# HT32F52352.net
KiCad netlist of a schematic drawn in Altium Designer
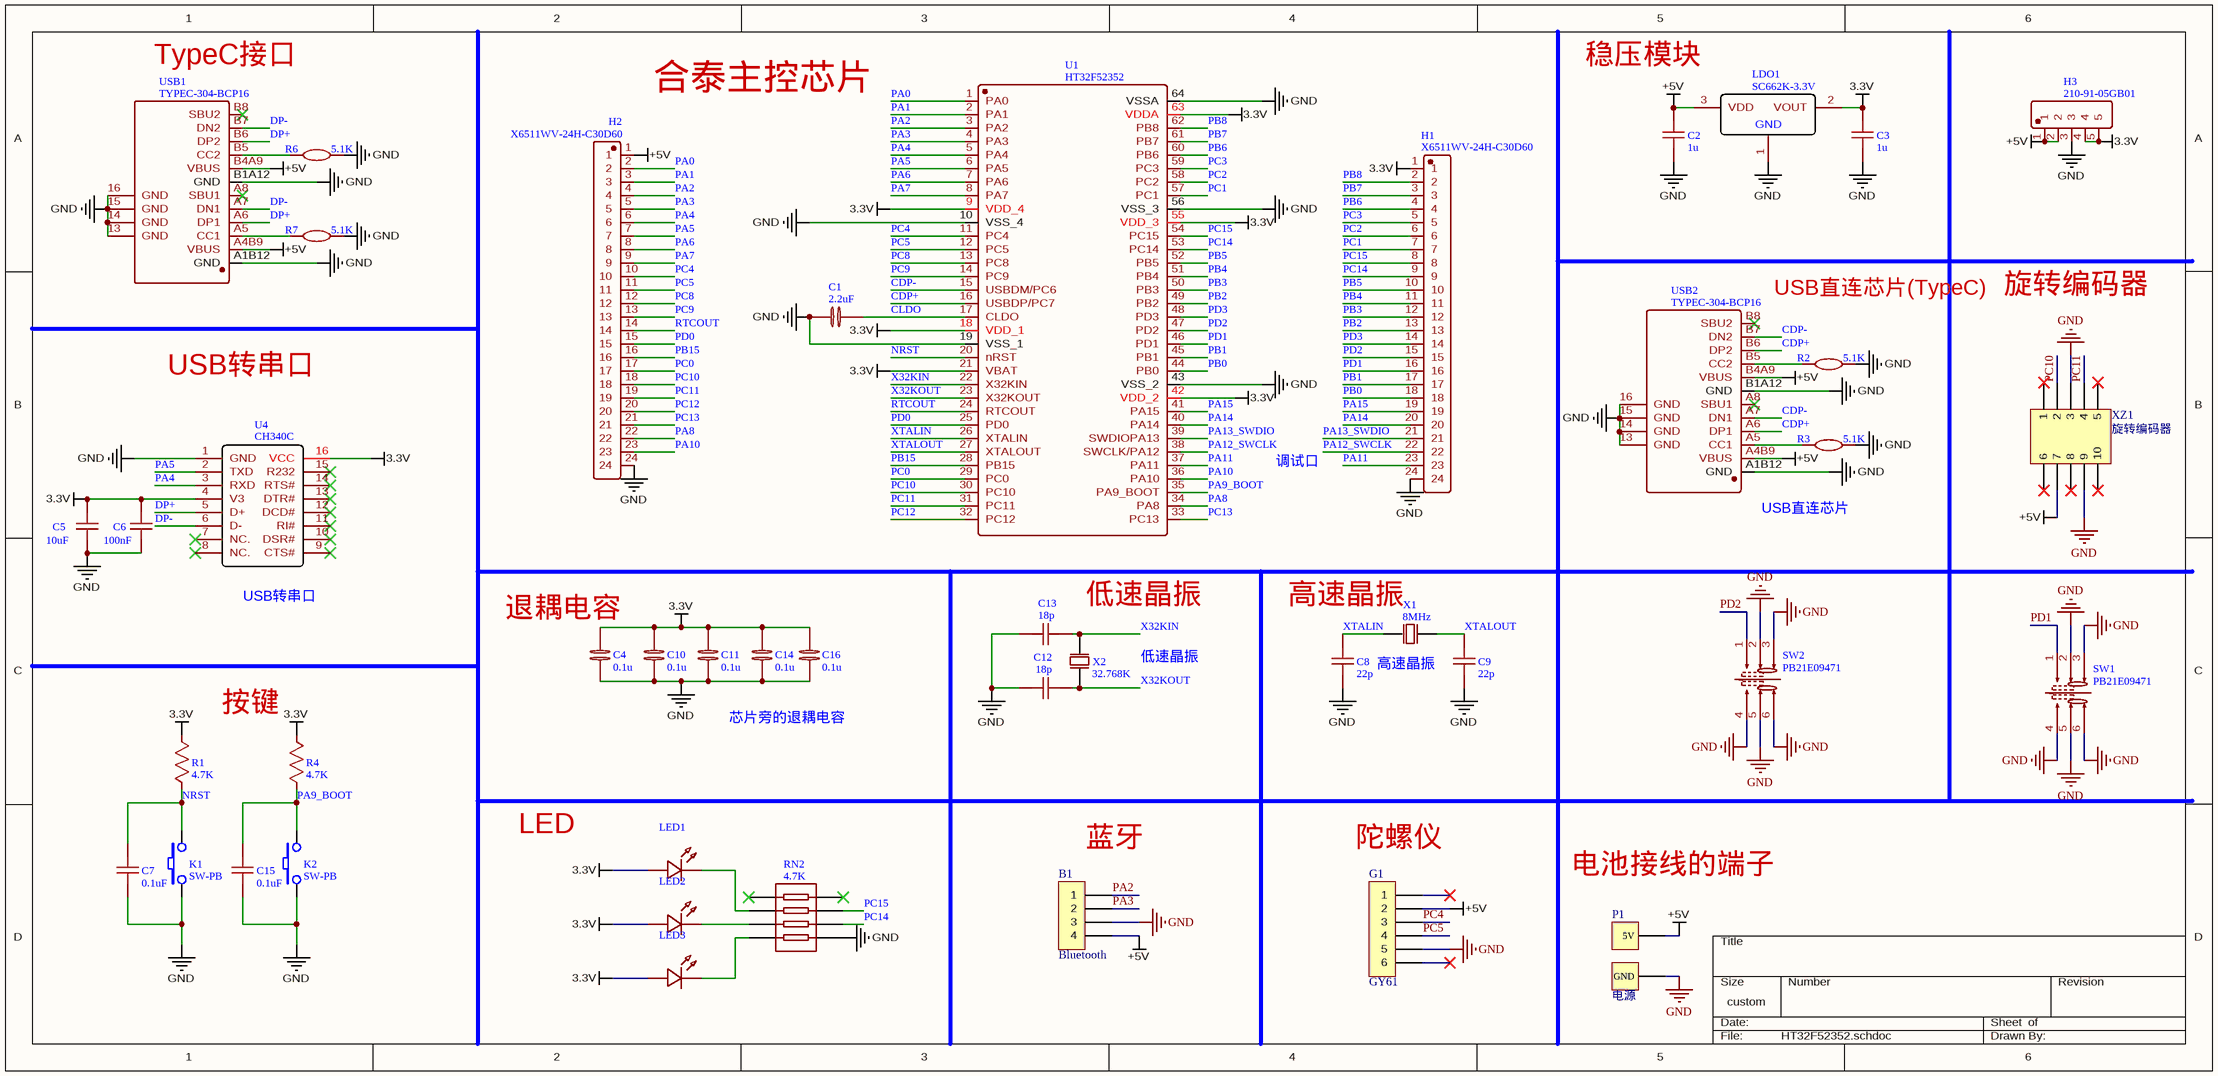
[diagram p0: HT32F52352.schdoc]

(export (version "E")
  (design (tool "Eeschema 10.0.6"))
  (components
    (comp (ref "B1") (value "Bluetooth") (footprint "HDR1X4") (libsource (lib "HT32") (part "Bluetooth")))
    (comp (ref "C1")
      (value "2.2uF")
      (footprint "0805_C")
      (fields (field (name "CONTRIBUTOR") "LCEDA_Lib"))
      (libsource (lib "altium-import") (part "root_0_2.2uF_"))
    )
    (comp (ref "C2")
      (value "1u")
      (footprint "0805_C")
      (fields (field (name "CONTRIBUTOR") "LCEDA_Lib"))
      (libsource (lib "altium-import") (part "root_1_1u_"))
    )
    (comp (ref "C3")
      (value "1u")
      (footprint "0805_C")
      (fields (field (name "CONTRIBUTOR") "LCEDA_Lib"))
      (libsource (lib "altium-import") (part "root_1_1u_"))
    )
    (comp (ref "C4")
      (value "0.1u")
      (footprint "0805_C")
      (fields (field (name "CONTRIBUTOR") "LCEDA_Lib"))
      (libsource (lib "altium-import") (part "root_1_0.1u_"))
    )
    (comp (ref "C5")
      (value "10uF")
      (footprint "0805_C")
      (libsource (lib "altium-import") (part "root_0_10uF_"))
    )
    (comp (ref "C6")
      (value "100nF")
      (footprint "0805_C")
      (libsource (lib "altium-import") (part "root_2_100nF_"))
    )
    (comp (ref "C7")
      (value "0.1uF")
      (footprint "0805_C")
      (libsource (lib "altium-import") (part "root_0_0.1uF_"))
    )
    (comp (ref "C8")
      (value "22p")
      (footprint "0805_C")
      (fields (field (name "CONTRIBUTOR") "LCEDA_Lib"))
      (libsource (lib "altium-import") (part "root_1_22p_"))
    )
    (comp (ref "C9")
      (value "22p")
      (footprint "0805_C")
      (fields (field (name "CONTRIBUTOR") "LCEDA_Lib"))
      (libsource (lib "altium-import") (part "root_1_22p_"))
    )
    (comp (ref "C10")
      (value "0.1u")
      (footprint "0805_C")
      (fields (field (name "CONTRIBUTOR") "LCEDA_Lib"))
      (libsource (lib "altium-import") (part "root_1_0.1u_"))
    )
    (comp (ref "C11")
      (value "0.1u")
      (footprint "0805_C")
      (fields (field (name "CONTRIBUTOR") "LCEDA_Lib"))
      (libsource (lib "altium-import") (part "root_1_0.1u_"))
    )
    (comp (ref "C12")
      (value "18p")
      (footprint "0805_C")
      (fields (field (name "CONTRIBUTOR") "LCEDA_Lib"))
      (libsource (lib "") (part "root_0_18p__1"))
    )
    (comp (ref "C13")
      (value "18p")
      (footprint "0805_C")
      (fields (field (name "CONTRIBUTOR") "LCEDA_Lib"))
      (libsource (lib "altium-import") (part "root_0_18p_"))
    )
    (comp (ref "C14")
      (value "0.1u")
      (footprint "0805_C")
      (fields (field (name "CONTRIBUTOR") "LCEDA_Lib"))
      (libsource (lib "altium-import") (part "root_1_0.1u_"))
    )
    (comp (ref "C15")
      (value "0.1uF")
      (footprint "0805_C")
      (libsource (lib "altium-import") (part "root_0_0.1uF_"))
    )
    (comp (ref "C16")
      (value "0.1u")
      (footprint "0805_C")
      (fields (field (name "CONTRIBUTOR") "LCEDA_Lib"))
      (libsource (lib "altium-import") (part "root_1_0.1u_"))
    )
    (comp (ref "G1") (value "GY61") (footprint "HDR1X6") (libsource (lib "HT32") (part "GY61")))
    (comp (ref "H1")
      (value "X6511WV-24H-C30D60")
      (footprint "HDR-TH_24P-P2.54-V-M")
      (fields (field (name "BOM_SUPPLIER PART") "C725956") (field (name "CONTRIBUTOR") "LCSC"))
      (libsource (lib "altium-import") (part "root_0_X6511WV-24H-C30D60_"))
    )
    (comp (ref "H2")
      (value "X6511WV-24H-C30D60")
      (footprint "HDR-TH_24P-P2.54-V-M")
      (fields (field (name "BOM_SUPPLIER PART") "C725956") (field (name "CONTRIBUTOR") "LCSC"))
      (libsource (lib "") (part "root_0_X6511WV-24H-C30D60__1"))
    )
    (comp (ref "H3")
      (value "210-91-05GB01")
      (footprint "HDR-TH_5P-P2.54-V-M")
      (fields (field (name "BOM_SUPPLIER PART") "C390682") (field (name "CONTRIBUTOR") "LCSC"))
      (libsource (lib "altium-import") (part "root_1_210-91-05GB01_"))
    )
    (comp (ref "K1")
      (value "SW-PB")
      (footprint "SW-SMD_L6.1-W3.7-LS7.9")
      (fields (field (name "CONTRIBUTOR") "ZhangYonghui"))
      (libsource (lib "altium-import") (part "root_3_SW-PB_"))
    )
    (comp (ref "K2")
      (value "SW-PB")
      (footprint "SW-SMD_L6.1-W3.7-LS7.9")
      (fields (field (name "CONTRIBUTOR") "ZhangYonghui"))
      (libsource (lib "altium-import") (part "root_3_SW-PB_"))
    )
    (comp (ref "LDO1")
      (value "SC662K-3.3V")
      (footprint "SOT-23-3_L2.9-W1.3-P1.90-LS2.4-BR")
      (fields (field (name "BOM_SUPPLIER PART") "C83932"))
      (libsource (lib "altium-import") (part "root_0_SC662K-3.3V_"))
    )
    (comp (ref "LED1")
      (value "LED-0603_B")
      (footprint "LED0603_BLUE")
      (fields
        (field (name "BOM_MANUFACTURER PART") "19-217/BHC-ZL1M2RY/3T")
        (field (name "BOM_SUPPLIER PART") "C72041")
        (field (name "CONTRIBUTOR") "LCEDA_01")
      )
      (libsource (lib "altium-import") (part "root_0_LED-0603_B_"))
    )
    (comp (ref "LED2")
      (value "LED-0603_B")
      (footprint "LED0603_BLUE")
      (fields
        (field (name "BOM_MANUFACTURER PART") "19-217/BHC-ZL1M2RY/3T")
        (field (name "BOM_SUPPLIER PART") "C72041")
        (field (name "CONTRIBUTOR") "LCEDA_01")
      )
      (libsource (lib "altium-import") (part "root_0_LED-0603_B_"))
    )
    (comp (ref "LED3")
      (value "LED-0603_B")
      (footprint "LED0603_BLUE")
      (fields
        (field (name "BOM_MANUFACTURER PART") "19-217/BHC-ZL1M2RY/3T")
        (field (name "BOM_SUPPLIER PART") "C72041")
        (field (name "CONTRIBUTOR") "LCEDA_01")
      )
      (libsource (lib "altium-import") (part "root_0_LED-0603_B_"))
    )
    (comp (ref "P1")
      (value "电源")
      (footprint "PCBComponent_1 - duplicate")
      (libsource (lib "HT32") (part "电源"))
    )
    (comp (ref "R1")
      (value "4.7K")
      (footprint "0805_R")
      (fields (field (name "CONTRIBUTOR") "LCEDA_Lib"))
      (libsource (lib "altium-import") (part "root_1_4.7K_"))
    )
    (comp (ref "R2")
      (value "5.1K")
      (footprint "0805_R")
      (libsource (lib "altium-import") (part "root_2_5.1K_"))
    )
    (comp (ref "R3")
      (value "5.1K")
      (footprint "0805_R")
      (libsource (lib "altium-import") (part "root_2_5.1K_"))
    )
    (comp (ref "R4")
      (value "4.7K")
      (footprint "0805_R")
      (fields (field (name "CONTRIBUTOR") "LCEDA_Lib"))
      (libsource (lib "altium-import") (part "root_1_4.7K_"))
    )
    (comp (ref "R6")
      (value "5.1K")
      (footprint "0805_R")
      (libsource (lib "altium-import") (part "root_2_5.1K_"))
    )
    (comp (ref "R7")
      (value "5.1K")
      (footprint "0805_R")
      (libsource (lib "altium-import") (part "root_2_5.1K_"))
    )
    (comp (ref "RN2")
      (value "4.7K")
      (footprint "RES-ARRAY-SMD_0603-8P-L3.2-W1.6-BL")
      (fields
        (field (name "BOM_SUPPLIER PART") "C194232")
        (field (name "BOM_MANUFACTURER PART") "EXB-38V472JV")
        (field (name "CONTRIBUTOR") "LCSC")
      )
      (libsource (lib "altium-import") (part "root_0_4.7K_"))
    )
    (comp (ref "SW1")
      (value "PB21E09471")
      (footprint "SW-TH_6P-L8.5-W8.5-P2.50-LS5.5-BL")
      (fields (field (name "BOM_SUPPLIER PART") "C194403") (field (name "CONTRIBUTOR") "LCSC"))
      (libsource (lib "HT32") (part "PB21E09471"))
    )
    (comp (ref "SW2")
      (value "PB21E09471")
      (footprint "SW-TH_6P-L8.5-W8.5-P2.50-LS5.5-BL")
      (fields (field (name "BOM_SUPPLIER PART") "C194403") (field (name "CONTRIBUTOR") "LCSC"))
      (libsource (lib "HT32") (part "PB21E09471"))
    )
    (comp (ref "U1")
      (value "HT32F52352")
      (footprint "LQFP-64_L7.0-W7.0-P0.40-LS9.2-BL")
      (fields (field (name "BOM_SUPPLIER PART") "C97188"))
      (libsource (lib "altium-import") (part "root_0_HT32F52352_"))
    )
    (comp (ref "U4")
      (value "CH340C")
      (footprint "SOP-16_L10.0-W3.9-P1.27-LS6.0-BL")
      (fields (field (name "BOM_SUPPLIER PART") "C84681"))
      (libsource (lib "altium-import") (part "root_0_CH340C_"))
    )
    (comp (ref "USB1")
      (value "TYPEC-304-BCP16")
      (footprint "USB-C-SMD_TYPEC-304-BCP16")
      (fields (field (name "BOM_SUPPLIER PART") "C720629") (field (name "CONTRIBUTOR") "LCSC"))
      (libsource (lib "altium-import") (part "root_2_TYPEC-304-BCP16_"))
    )
    (comp (ref "USB2")
      (value "TYPEC-304-BCP16")
      (footprint "USB-C-SMD_TYPEC-304-BCP16")
      (fields (field (name "BOM_SUPPLIER PART") "C720629") (field (name "CONTRIBUTOR") "LCSC"))
      (libsource (lib "altium-import") (part "root_2_TYPEC-304-BCP16_"))
    )
    (comp (ref "X1")
      (value "8MHz")
      (footprint "HC-49S_L11.4-W4.8")
      (fields
        (field (name "BOM_SUPPLIER PART") "C107426")
        (field (name "BOM_MANUFACTURER PART") "HC-49SM8MHz20pF30ppm")
        (field (name "CONTRIBUTOR") "LCSC")
      )
      (libsource (lib "altium-import") (part "root_0_8MHz_"))
    )
    (comp (ref "X2")
      (value "32.768K")
      (footprint "OSC-TH_BD3.1-P0.8-D0.3")
      (fields
        (field (name "BOM_SUPPLIER PART") "C213421")
        (field (name "BOM_MANUFACTURER PART") "1TC125DFNS019")
        (field (name "CONTRIBUTOR") "LCSC")
      )
      (libsource (lib "altium-import") (part "root_3_32.768K_"))
    )
    (comp (ref "XZ1") (value "旋转编码器") (footprint "rotary encoder") (libsource (lib "HT32") (part "旋转编码器")))
  )
  (nets
    (net (code "1") (name "+5V") (class "Default")
      (node (ref "B1") (pin "4") (pinfunction "4_4") (pintype "passive"))
      (node (ref "C2") (pin "2") (pinfunction "2_2") (pintype "passive"))
      (node (ref "G1") (pin "2") (pinfunction "2_2") (pintype "passive"))
      (node (ref "H2") (pin "1") (pinfunction "1_1") (pintype "passive"))
      (node (ref "H3") (pin "1") (pinfunction "1_1") (pintype "passive"))
      (node (ref "H3") (pin "2") (pinfunction "2_2") (pintype "passive"))
      (node (ref "LDO1") (pin "3") (pinfunction "VDD_3") (pintype "passive"))
      (node (ref "P1") (pin "1") (pinfunction "5V_1") (pintype "passive"))
      (node (ref "USB1") (pin "A4B9") (pinfunction "VBUS_A4B9") (pintype "passive"))
      (node (ref "USB1") (pin "B4A9") (pinfunction "VBUS_B4A9") (pintype "passive"))
      (node (ref "USB2") (pin "A4B9") (pinfunction "VBUS_A4B9") (pintype "passive"))
      (node (ref "USB2") (pin "B4A9") (pinfunction "VBUS_B4A9") (pintype "passive"))
      (node (ref "XZ1") (pin "7") (pinfunction "7_7") (pintype "passive"))
    )
    (net (code "2") (name "/CDP+") (class "Default")
      (node (ref "U1") (pin "16") (pinfunction "USBDP/PC7_16") (pintype "passive"))
      (node (ref "USB2") (pin "A6") (pinfunction "DP1_A6") (pintype "passive"))
      (node (ref "USB2") (pin "B6") (pinfunction "DP2_B6") (pintype "passive"))
    )
    (net (code "3") (name "/CDP-") (class "Default")
      (node (ref "U1") (pin "15") (pinfunction "USBDM/PC6_15") (pintype "passive"))
      (node (ref "USB2") (pin "A7") (pinfunction "DN1_A7") (pintype "passive"))
      (node (ref "USB2") (pin "B7") (pinfunction "DN2_B7") (pintype "passive"))
    )
    (net (code "4") (name "/CLDO") (class "Default")
      (node (ref "C1") (pin "2") (pinfunction "2_2") (pintype "passive"))
      (node (ref "U1") (pin "17") (pinfunction "CLDO_17") (pintype "passive"))
    )
    (net (code "5") (name "/DP+") (class "Default")
      (node (ref "U4") (pin "5") (pinfunction "D+_5") (pintype "passive"))
      (node (ref "USB1") (pin "A6") (pinfunction "DP1_A6") (pintype "passive"))
      (node (ref "USB1") (pin "B6") (pinfunction "DP2_B6") (pintype "passive"))
    )
    (net (code "6") (name "/DP-") (class "Default")
      (node (ref "U4") (pin "6") (pinfunction "D-_6") (pintype "passive"))
      (node (ref "USB1") (pin "A7") (pinfunction "DN1_A7") (pintype "passive"))
      (node (ref "USB1") (pin "B7") (pinfunction "DN2_B7") (pintype "passive"))
    )
    (net (code "7") (name "/NRST") (class "Default")
      (node (ref "C7") (pin "2") (pinfunction "2_2") (pintype "passive"))
      (node (ref "K1") (pin "1") (pinfunction "1_1") (pintype "passive"))
      (node (ref "R1") (pin "1") (pinfunction "1_1") (pintype "passive"))
      (node (ref "U1") (pin "20") (pinfunction "nRST_20") (pintype "passive"))
    )
    (net (code "8") (name "/PA0") (class "Default")
      (node (ref "H2") (pin "2") (pinfunction "2_2") (pintype "passive"))
      (node (ref "U1") (pin "1") (pinfunction "PA0_1") (pintype "passive"))
    )
    (net (code "9") (name "/PA1") (class "Default")
      (node (ref "H2") (pin "3") (pinfunction "3_3") (pintype "passive"))
      (node (ref "U1") (pin "2") (pinfunction "PA1_2") (pintype "passive"))
    )
    (net (code "10") (name "/PA2") (class "Default")
      (node (ref "B1") (pin "1") (pinfunction "1_1") (pintype "passive"))
      (node (ref "H2") (pin "4") (pinfunction "4_4") (pintype "passive"))
      (node (ref "U1") (pin "3") (pinfunction "PA2_3") (pintype "passive"))
    )
    (net (code "11") (name "/PA3") (class "Default")
      (node (ref "B1") (pin "2") (pinfunction "2_2") (pintype "passive"))
      (node (ref "H2") (pin "5") (pinfunction "5_5") (pintype "passive"))
      (node (ref "U1") (pin "4") (pinfunction "PA3_4") (pintype "passive"))
    )
    (net (code "12") (name "/PA4") (class "Default")
      (node (ref "H2") (pin "6") (pinfunction "6_6") (pintype "passive"))
      (node (ref "U1") (pin "5") (pinfunction "PA4_5") (pintype "passive"))
      (node (ref "U4") (pin "3") (pinfunction "RXD_3") (pintype "passive"))
    )
    (net (code "13") (name "/PA5") (class "Default")
      (node (ref "H2") (pin "7") (pinfunction "7_7") (pintype "passive"))
      (node (ref "U1") (pin "6") (pinfunction "PA5_6") (pintype "passive"))
      (node (ref "U4") (pin "2") (pinfunction "TXD_2") (pintype "passive"))
    )
    (net (code "14") (name "/PA6") (class "Default")
      (node (ref "H2") (pin "8") (pinfunction "8_8") (pintype "passive"))
      (node (ref "U1") (pin "7") (pinfunction "PA6_7") (pintype "passive"))
    )
    (net (code "15") (name "/PA7") (class "Default")
      (node (ref "H2") (pin "9") (pinfunction "9_9") (pintype "passive"))
      (node (ref "U1") (pin "8") (pinfunction "PA7_8") (pintype "passive"))
    )
    (net (code "16") (name "/PA8") (class "Default")
      (node (ref "H2") (pin "22") (pinfunction "22_22") (pintype "passive"))
      (node (ref "U1") (pin "34") (pinfunction "PA8_34") (pintype "passive"))
    )
    (net (code "17") (name "/PA9_BOOT") (class "Default")
      (node (ref "C15") (pin "2") (pinfunction "2_2") (pintype "passive"))
      (node (ref "K2") (pin "1") (pinfunction "1_1") (pintype "passive"))
      (node (ref "R4") (pin "1") (pinfunction "1_1") (pintype "passive"))
      (node (ref "U1") (pin "35") (pinfunction "PA9_BOOT_35") (pintype "passive"))
    )
    (net (code "18") (name "/PA10") (class "Default")
      (node (ref "H2") (pin "23") (pinfunction "23_23") (pintype "passive"))
      (node (ref "U1") (pin "36") (pinfunction "PA10_36") (pintype "passive"))
    )
    (net (code "19") (name "/PA11") (class "Default")
      (node (ref "H1") (pin "23") (pinfunction "23_23") (pintype "passive"))
      (node (ref "U1") (pin "37") (pinfunction "PA11_37") (pintype "passive"))
    )
    (net (code "20") (name "/PA12_SWCLK") (class "Default")
      (node (ref "H1") (pin "22") (pinfunction "22_22") (pintype "passive"))
      (node (ref "U1") (pin "38") (pinfunction "SWCLK/PA12_38") (pintype "passive"))
    )
    (net (code "21") (name "/PA13_SWDIO") (class "Default")
      (node (ref "H1") (pin "21") (pinfunction "21_21") (pintype "passive"))
      (node (ref "U1") (pin "39") (pinfunction "SWDIOPA13_39") (pintype "passive"))
    )
    (net (code "22") (name "/PA14") (class "Default")
      (node (ref "H1") (pin "20") (pinfunction "20_20") (pintype "passive"))
      (node (ref "U1") (pin "40") (pinfunction "PA14_40") (pintype "passive"))
    )
    (net (code "23") (name "/PA15") (class "Default")
      (node (ref "H1") (pin "19") (pinfunction "19_19") (pintype "passive"))
      (node (ref "U1") (pin "41") (pinfunction "PA15_41") (pintype "passive"))
    )
    (net (code "24") (name "/PB0") (class "Default")
      (node (ref "H1") (pin "18") (pinfunction "18_18") (pintype "passive"))
      (node (ref "U1") (pin "44") (pinfunction "PB0_44") (pintype "passive"))
    )
    (net (code "25") (name "/PB1") (class "Default")
      (node (ref "H1") (pin "17") (pinfunction "17_17") (pintype "passive"))
      (node (ref "U1") (pin "45") (pinfunction "PB1_45") (pintype "passive"))
    )
    (net (code "26") (name "/PB2") (class "Default")
      (node (ref "H1") (pin "13") (pinfunction "13_13") (pintype "passive"))
      (node (ref "U1") (pin "49") (pinfunction "PB2_49") (pintype "passive"))
    )
    (net (code "27") (name "/PB3") (class "Default")
      (node (ref "H1") (pin "12") (pinfunction "12_12") (pintype "passive"))
      (node (ref "U1") (pin "50") (pinfunction "PB3_50") (pintype "passive"))
    )
    (net (code "28") (name "/PB4") (class "Default")
      (node (ref "H1") (pin "11") (pinfunction "11_11") (pintype "passive"))
      (node (ref "U1") (pin "51") (pinfunction "PB4_51") (pintype "passive"))
    )
    (net (code "29") (name "/PB5") (class "Default")
      (node (ref "H1") (pin "10") (pinfunction "10_10") (pintype "passive"))
      (node (ref "U1") (pin "52") (pinfunction "PB5_52") (pintype "passive"))
    )
    (net (code "30") (name "/PB6") (class "Default")
      (node (ref "H1") (pin "4") (pinfunction "4_4") (pintype "passive"))
      (node (ref "U1") (pin "60") (pinfunction "PB6_60") (pintype "passive"))
    )
    (net (code "31") (name "/PB7") (class "Default")
      (node (ref "H1") (pin "3") (pinfunction "3_3") (pintype "passive"))
      (node (ref "U1") (pin "61") (pinfunction "PB7_61") (pintype "passive"))
    )
    (net (code "32") (name "/PB8") (class "Default")
      (node (ref "H1") (pin "2") (pinfunction "2_2") (pintype "passive"))
      (node (ref "U1") (pin "62") (pinfunction "PB8_62") (pintype "passive"))
    )
    (net (code "33") (name "/PB15") (class "Default")
      (node (ref "H2") (pin "16") (pinfunction "16_16") (pintype "passive"))
      (node (ref "U1") (pin "28") (pinfunction "PB15_28") (pintype "passive"))
    )
    (net (code "34") (name "/PC0") (class "Default")
      (node (ref "H2") (pin "17") (pinfunction "17_17") (pintype "passive"))
      (node (ref "U1") (pin "29") (pinfunction "PC0_29") (pintype "passive"))
    )
    (net (code "35") (name "/PC1") (class "Default")
      (node (ref "H1") (pin "7") (pinfunction "7_7") (pintype "passive"))
      (node (ref "U1") (pin "57") (pinfunction "PC1_57") (pintype "passive"))
    )
    (net (code "36") (name "/PC2") (class "Default")
      (node (ref "H1") (pin "6") (pinfunction "6_6") (pintype "passive"))
      (node (ref "U1") (pin "58") (pinfunction "PC2_58") (pintype "passive"))
    )
    (net (code "37") (name "/PC3") (class "Default")
      (node (ref "H1") (pin "5") (pinfunction "5_5") (pintype "passive"))
      (node (ref "U1") (pin "59") (pinfunction "PC3_59") (pintype "passive"))
    )
    (net (code "38") (name "/PC4") (class "Default")
      (node (ref "G1") (pin "3") (pinfunction "3_3") (pintype "passive"))
      (node (ref "H2") (pin "10") (pinfunction "10_10") (pintype "passive"))
      (node (ref "U1") (pin "11") (pinfunction "PC4_11") (pintype "passive"))
    )
    (net (code "39") (name "/PC5") (class "Default")
      (node (ref "G1") (pin "4") (pinfunction "4_4") (pintype "passive"))
      (node (ref "H2") (pin "11") (pinfunction "11_11") (pintype "passive"))
      (node (ref "U1") (pin "12") (pinfunction "PC5_12") (pintype "passive"))
    )
    (net (code "40") (name "/PC8") (class "Default")
      (node (ref "H2") (pin "12") (pinfunction "12_12") (pintype "passive"))
      (node (ref "U1") (pin "13") (pinfunction "PC8_13") (pintype "passive"))
    )
    (net (code "41") (name "/PC9") (class "Default")
      (node (ref "H2") (pin "13") (pinfunction "13_13") (pintype "passive"))
      (node (ref "U1") (pin "14") (pinfunction "PC9_14") (pintype "passive"))
    )
    (net (code "42") (name "/PC10") (class "Default")
      (node (ref "H2") (pin "18") (pinfunction "18_18") (pintype "passive"))
      (node (ref "U1") (pin "30") (pinfunction "PC10_30") (pintype "passive"))
      (node (ref "XZ1") (pin "2") (pinfunction "2_2") (pintype "passive"))
    )
    (net (code "43") (name "/PC11") (class "Default")
      (node (ref "H2") (pin "19") (pinfunction "19_19") (pintype "passive"))
      (node (ref "U1") (pin "31") (pinfunction "PC11_31") (pintype "passive"))
      (node (ref "XZ1") (pin "4") (pinfunction "4_4") (pintype "passive"))
    )
    (net (code "44") (name "/PC12") (class "Default")
      (node (ref "H2") (pin "20") (pinfunction "20_20") (pintype "passive"))
      (node (ref "U1") (pin "32") (pinfunction "PC12_32") (pintype "passive"))
    )
    (net (code "45") (name "/PC13") (class "Default")
      (node (ref "H2") (pin "21") (pinfunction "21_21") (pintype "passive"))
      (node (ref "U1") (pin "33") (pinfunction "PC13_33") (pintype "passive"))
    )
    (net (code "46") (name "/PC14") (class "Default")
      (node (ref "H1") (pin "9") (pinfunction "9_9") (pintype "passive"))
      (node (ref "RN2") (pin "6") (pinfunction "6_6") (pintype "passive"))
      (node (ref "U1") (pin "53") (pinfunction "PC14_53") (pintype "passive"))
    )
    (net (code "47") (name "/PC15") (class "Default")
      (node (ref "H1") (pin "8") (pinfunction "8_8") (pintype "passive"))
      (node (ref "RN2") (pin "7") (pinfunction "7_7") (pintype "passive"))
      (node (ref "U1") (pin "54") (pinfunction "PC15_54") (pintype "passive"))
    )
    (net (code "48") (name "/PD0") (class "Default")
      (node (ref "H2") (pin "15") (pinfunction "15_15") (pintype "passive"))
      (node (ref "U1") (pin "25") (pinfunction "PD0_25") (pintype "passive"))
    )
    (net (code "49") (name "/PD1") (class "Default")
      (node (ref "H1") (pin "16") (pinfunction "16_16") (pintype "passive"))
      (node (ref "SW1") (pin "1") (pinfunction "1_1") (pintype "passive"))
      (node (ref "U1") (pin "46") (pinfunction "PD1_46") (pintype "passive"))
    )
    (net (code "50") (name "/PD2") (class "Default")
      (node (ref "H1") (pin "15") (pinfunction "15_15") (pintype "passive"))
      (node (ref "SW2") (pin "1") (pinfunction "1_1") (pintype "passive"))
      (node (ref "U1") (pin "47") (pinfunction "PD2_47") (pintype "passive"))
    )
    (net (code "51") (name "/PD3") (class "Default")
      (node (ref "H1") (pin "14") (pinfunction "14_14") (pintype "passive"))
      (node (ref "U1") (pin "48") (pinfunction "PD3_48") (pintype "passive"))
    )
    (net (code "52") (name "/RTCOUT") (class "Default")
      (node (ref "H2") (pin "14") (pinfunction "14_14") (pintype "passive"))
      (node (ref "U1") (pin "24") (pinfunction "RTCOUT_24") (pintype "passive"))
    )
    (net (code "53") (name "/X32KIN") (class "Default")
      (node (ref "C13") (pin "2") (pinfunction "2_2") (pintype "passive"))
      (node (ref "U1") (pin "22") (pinfunction "X32KIN_22") (pintype "passive"))
      (node (ref "X2") (pin "1") (pinfunction "OSC1_1") (pintype "passive"))
    )
    (net (code "54") (name "/X32KOUT") (class "Default")
      (node (ref "C12") (pin "1") (pinfunction "1_1") (pintype "passive"))
      (node (ref "U1") (pin "23") (pinfunction "X32KOUT_23") (pintype "passive"))
      (node (ref "X2") (pin "2") (pinfunction "OSC2_2") (pintype "passive"))
    )
    (net (code "55") (name "/XTALIN") (class "Default")
      (node (ref "C8") (pin "2") (pinfunction "2_2") (pintype "passive"))
      (node (ref "U1") (pin "26") (pinfunction "XTALIN_26") (pintype "passive"))
      (node (ref "X1") (pin "1") (pinfunction "OSC1_1") (pintype "passive"))
    )
    (net (code "56") (name "/XTALOUT") (class "Default")
      (node (ref "C9") (pin "2") (pinfunction "2_2") (pintype "passive"))
      (node (ref "U1") (pin "27") (pinfunction "XTALOUT_27") (pintype "passive"))
      (node (ref "X1") (pin "2") (pinfunction "OSC2_2") (pintype "passive"))
    )
    (net (code "57") (name "3.3V") (class "Default")
      (node (ref "C10") (pin "2") (pinfunction "2_2") (pintype "passive"))
      (node (ref "C11") (pin "2") (pinfunction "2_2") (pintype "passive"))
      (node (ref "C14") (pin "2") (pinfunction "2_2") (pintype "passive"))
      (node (ref "C16") (pin "2") (pinfunction "2_2") (pintype "passive"))
      (node (ref "C3") (pin "2") (pinfunction "2_2") (pintype "passive"))
      (node (ref "C4") (pin "2") (pinfunction "2_2") (pintype "passive"))
      (node (ref "C5") (pin "2") (pinfunction "2_2") (pintype "passive"))
      (node (ref "C6") (pin "1") (pinfunction "1_1") (pintype "passive"))
      (node (ref "H1") (pin "1") (pinfunction "1_1") (pintype "passive"))
      (node (ref "H3") (pin "4") (pinfunction "4_4") (pintype "passive"))
      (node (ref "H3") (pin "5") (pinfunction "5_5") (pintype "passive"))
      (node (ref "LDO1") (pin "2") (pinfunction "VOUT_2") (pintype "passive"))
      (node (ref "LED1") (pin "1") (pinfunction "1_1") (pintype "passive"))
      (node (ref "LED2") (pin "1") (pinfunction "1_1") (pintype "passive"))
      (node (ref "LED3") (pin "1") (pinfunction "1_1") (pintype "passive"))
      (node (ref "R1") (pin "2") (pinfunction "2_2") (pintype "passive"))
      (node (ref "R4") (pin "2") (pinfunction "2_2") (pintype "passive"))
      (node (ref "U1") (pin "18") (pinfunction "VDD_1_18") (pintype "passive"))
      (node (ref "U1") (pin "21") (pinfunction "VBAT_21") (pintype "passive"))
      (node (ref "U1") (pin "42") (pinfunction "VDD_2_42") (pintype "passive"))
      (node (ref "U1") (pin "55") (pinfunction "VDD_3_55") (pintype "passive"))
      (node (ref "U1") (pin "63") (pinfunction "VDDA_63") (pintype "passive"))
      (node (ref "U1") (pin "9") (pinfunction "VDD_4_9") (pintype "passive"))
      (node (ref "U4") (pin "16") (pinfunction "VCC_16") (pintype "passive"))
      (node (ref "U4") (pin "4") (pinfunction "V3_4") (pintype "passive"))
    )
    (net (code "58") (name "GND") (class "Default")
      (node (ref "B1") (pin "3") (pinfunction "3_3") (pintype "passive"))
      (node (ref "C1") (pin "1") (pinfunction "1_1") (pintype "passive"))
      (node (ref "C10") (pin "1") (pinfunction "1_1") (pintype "passive"))
      (node (ref "C11") (pin "1") (pinfunction "1_1") (pintype "passive"))
      (node (ref "C12") (pin "2") (pinfunction "2_2") (pintype "passive"))
      (node (ref "C13") (pin "1") (pinfunction "1_1") (pintype "passive"))
      (node (ref "C14") (pin "1") (pinfunction "1_1") (pintype "passive"))
      (node (ref "C15") (pin "1") (pinfunction "1_1") (pintype "passive"))
      (node (ref "C16") (pin "1") (pinfunction "1_1") (pintype "passive"))
      (node (ref "C2") (pin "1") (pinfunction "1_1") (pintype "passive"))
      (node (ref "C3") (pin "1") (pinfunction "1_1") (pintype "passive"))
      (node (ref "C4") (pin "1") (pinfunction "1_1") (pintype "passive"))
      (node (ref "C5") (pin "1") (pinfunction "1_1") (pintype "passive"))
      (node (ref "C6") (pin "2") (pinfunction "2_2") (pintype "passive"))
      (node (ref "C7") (pin "1") (pinfunction "1_1") (pintype "passive"))
      (node (ref "C8") (pin "1") (pinfunction "1_1") (pintype "passive"))
      (node (ref "C9") (pin "1") (pinfunction "1_1") (pintype "passive"))
      (node (ref "G1") (pin "5") (pinfunction "5_5") (pintype "passive"))
      (node (ref "H1") (pin "24") (pinfunction "24_24") (pintype "passive"))
      (node (ref "H2") (pin "24") (pinfunction "24_24") (pintype "passive"))
      (node (ref "H3") (pin "3") (pinfunction "3_3") (pintype "passive"))
      (node (ref "K1") (pin "2") (pinfunction "2_2") (pintype "passive"))
      (node (ref "K2") (pin "2") (pinfunction "2_2") (pintype "passive"))
      (node (ref "LDO1") (pin "1") (pinfunction "GND_1") (pintype "passive"))
      (node (ref "P1") (pin "2") (pinfunction "GND_2") (pintype "passive"))
      (node (ref "R2") (pin "1") (pinfunction "1_1") (pintype "passive"))
      (node (ref "R3") (pin "1") (pinfunction "1_1") (pintype "passive"))
      (node (ref "R6") (pin "1") (pinfunction "1_1") (pintype "passive"))
      (node (ref "R7") (pin "1") (pinfunction "1_1") (pintype "passive"))
      (node (ref "RN2") (pin "5") (pinfunction "5_5") (pintype "passive"))
      (node (ref "SW1") (pin "2") (pinfunction "2_2") (pintype "passive"))
      (node (ref "SW1") (pin "3") (pinfunction "3_3") (pintype "passive"))
      (node (ref "SW1") (pin "4") (pinfunction "4_4") (pintype "passive"))
      (node (ref "SW1") (pin "5") (pinfunction "5_5") (pintype "passive"))
      (node (ref "SW1") (pin "6") (pinfunction "6_6") (pintype "passive"))
      (node (ref "SW2") (pin "2") (pinfunction "2_2") (pintype "passive"))
      (node (ref "SW2") (pin "3") (pinfunction "3_3") (pintype "passive"))
      (node (ref "SW2") (pin "4") (pinfunction "4_4") (pintype "passive"))
      (node (ref "SW2") (pin "5") (pinfunction "5_5") (pintype "passive"))
      (node (ref "SW2") (pin "6") (pinfunction "6_6") (pintype "passive"))
      (node (ref "U1") (pin "10") (pinfunction "VSS_4_10") (pintype "passive"))
      (node (ref "U1") (pin "19") (pinfunction "VSS_1_19") (pintype "passive"))
      (node (ref "U1") (pin "43") (pinfunction "VSS_2_43") (pintype "passive"))
      (node (ref "U1") (pin "56") (pinfunction "VSS_3_56") (pintype "passive"))
      (node (ref "U1") (pin "64") (pinfunction "VSSA_64") (pintype "passive"))
      (node (ref "U4") (pin "1") (pinfunction "GND_1") (pintype "passive"))
      (node (ref "USB1") (pin "13") (pinfunction "GND_13") (pintype "passive"))
      (node (ref "USB1") (pin "14") (pinfunction "GND_14") (pintype "passive"))
      (node (ref "USB1") (pin "15") (pinfunction "GND_15") (pintype "passive"))
      (node (ref "USB1") (pin "16") (pinfunction "GND_16") (pintype "passive"))
      (node (ref "USB1") (pin "A1B12") (pinfunction "GND_A1B12") (pintype "passive"))
      (node (ref "USB1") (pin "B1A12") (pinfunction "GND_B1A12") (pintype "passive"))
      (node (ref "USB2") (pin "13") (pinfunction "GND_13") (pintype "passive"))
      (node (ref "USB2") (pin "14") (pinfunction "GND_14") (pintype "passive"))
      (node (ref "USB2") (pin "15") (pinfunction "GND_15") (pintype "passive"))
      (node (ref "USB2") (pin "16") (pinfunction "GND_16") (pintype "passive"))
      (node (ref "USB2") (pin "A1B12") (pinfunction "GND_A1B12") (pintype "passive"))
      (node (ref "USB2") (pin "B1A12") (pinfunction "GND_B1A12") (pintype "passive"))
      (node (ref "XZ1") (pin "3") (pinfunction "3_3") (pintype "passive"))
      (node (ref "XZ1") (pin "9") (pinfunction "9_9") (pintype "passive"))
    )
    (net (code "59") (name "Net-(LED1-Pad2)") (class "Default")
      (node (ref "LED1") (pin "2") (pinfunction "2_2") (pintype "passive"))
      (node (ref "RN2") (pin "2") (pinfunction "2_2") (pintype "passive"))
    )
    (net (code "60") (name "Net-(LED2-Pad2)") (class "Default")
      (node (ref "LED2") (pin "2") (pinfunction "2_2") (pintype "passive"))
      (node (ref "RN2") (pin "3") (pinfunction "3_3") (pintype "passive"))
    )
    (net (code "61") (name "Net-(LED3-Pad2)") (class "Default")
      (node (ref "LED3") (pin "2") (pinfunction "2_2") (pintype "passive"))
      (node (ref "RN2") (pin "4") (pinfunction "4_4") (pintype "passive"))
    )
    (net (code "62") (name "Net-(USB1-CC1)") (class "Default")
      (node (ref "R7") (pin "2") (pinfunction "2_2") (pintype "passive"))
      (node (ref "USB1") (pin "A5") (pinfunction "CC1_A5") (pintype "passive"))
    )
    (net (code "63") (name "Net-(USB1-CC2)") (class "Default")
      (node (ref "R6") (pin "2") (pinfunction "2_2") (pintype "passive"))
      (node (ref "USB1") (pin "B5") (pinfunction "CC2_B5") (pintype "passive"))
    )
    (net (code "64") (name "Net-(USB2-CC1)") (class "Default")
      (node (ref "R3") (pin "2") (pinfunction "2_2") (pintype "passive"))
      (node (ref "USB2") (pin "A5") (pinfunction "CC1_A5") (pintype "passive"))
    )
    (net (code "65") (name "Net-(USB2-CC2)") (class "Default")
      (node (ref "R2") (pin "2") (pinfunction "2_2") (pintype "passive"))
      (node (ref "USB2") (pin "B5") (pinfunction "CC2_B5") (pintype "passive"))
    )
    (net (code "66") (name "unconnected-(G1-Pad1)") (class "Default")
      (node (ref "G1") (pin "1") (pinfunction "1_1") (pintype "passive+no_connect"))
    )
    (net (code "67") (name "unconnected-(G1-Pad6)") (class "Default")
      (node (ref "G1") (pin "6") (pinfunction "6_6") (pintype "passive+no_connect"))
    )
    (net (code "68") (name "unconnected-(RN2-Pad1)") (class "Default")
      (node (ref "RN2") (pin "1") (pinfunction "1_1") (pintype "passive+no_connect"))
    )
    (net (code "69") (name "unconnected-(RN2-Pad8)") (class "Default")
      (node (ref "RN2") (pin "8") (pinfunction "8_8") (pintype "passive+no_connect"))
    )
    (net (code "70") (name "unconnected-(U4-CTS#-Pad9)") (class "Default")
      (node (ref "U4") (pin "9") (pinfunction "CTS#_9") (pintype "passive+no_connect"))
    )
    (net (code "71") (name "unconnected-(U4-DCD#-Pad12)") (class "Default")
      (node (ref "U4") (pin "12") (pinfunction "DCD#_12") (pintype "passive+no_connect"))
    )
    (net (code "72") (name "unconnected-(U4-DSR#-Pad10)") (class "Default")
      (node (ref "U4") (pin "10") (pinfunction "DSR#_10") (pintype "passive+no_connect"))
    )
    (net (code "73") (name "unconnected-(U4-DTR#-Pad13)") (class "Default")
      (node (ref "U4") (pin "13") (pinfunction "DTR#_13") (pintype "passive+no_connect"))
    )
    (net (code "74") (name "unconnected-(U4-NC.-Pad7)") (class "Default")
      (node (ref "U4") (pin "7") (pinfunction "NC._7") (pintype "passive+no_connect"))
    )
    (net (code "75") (name "unconnected-(U4-NC.-Pad8)") (class "Default")
      (node (ref "U4") (pin "8") (pinfunction "NC._8") (pintype "passive+no_connect"))
    )
    (net (code "76") (name "unconnected-(U4-R232-Pad15)") (class "Default")
      (node (ref "U4") (pin "15") (pinfunction "R232_15") (pintype "passive+no_connect"))
    )
    (net (code "77") (name "unconnected-(U4-RI#-Pad11)") (class "Default")
      (node (ref "U4") (pin "11") (pinfunction "RI#_11") (pintype "passive+no_connect"))
    )
    (net (code "78") (name "unconnected-(U4-RTS#-Pad14)") (class "Default")
      (node (ref "U4") (pin "14") (pinfunction "RTS#_14") (pintype "passive+no_connect"))
    )
    (net (code "79") (name "unconnected-(USB1-SBU1-PadA8)") (class "Default")
      (node (ref "USB1") (pin "A8") (pinfunction "SBU1_A8") (pintype "passive+no_connect"))
    )
    (net (code "80") (name "unconnected-(USB1-SBU2-PadB8)") (class "Default")
      (node (ref "USB1") (pin "B8") (pinfunction "SBU2_B8") (pintype "passive+no_connect"))
    )
    (net (code "81") (name "unconnected-(USB2-SBU1-PadA8)") (class "Default")
      (node (ref "USB2") (pin "A8") (pinfunction "SBU1_A8") (pintype "passive+no_connect"))
    )
    (net (code "82") (name "unconnected-(USB2-SBU2-PadB8)") (class "Default")
      (node (ref "USB2") (pin "B8") (pinfunction "SBU2_B8") (pintype "passive+no_connect"))
    )
    (net (code "83") (name "unconnected-(XZ1-Pad1)") (class "Default")
      (node (ref "XZ1") (pin "1") (pinfunction "1_1") (pintype "passive+no_connect"))
    )
    (net (code "84") (name "unconnected-(XZ1-Pad5)") (class "Default")
      (node (ref "XZ1") (pin "5") (pinfunction "5_5") (pintype "passive+no_connect"))
    )
    (net (code "85") (name "unconnected-(XZ1-Pad6)") (class "Default")
      (node (ref "XZ1") (pin "6") (pinfunction "6_6") (pintype "passive+no_connect"))
    )
    (net (code "86") (name "unconnected-(XZ1-Pad8)") (class "Default")
      (node (ref "XZ1") (pin "8") (pinfunction "8_8") (pintype "passive+no_connect"))
    )
    (net (code "87") (name "unconnected-(XZ1-Pad10)") (class "Default")
      (node (ref "XZ1") (pin "10") (pinfunction "10_10") (pintype "passive+no_connect"))
    )
  )
)
